# panel-mount-orafice-mk-1.net
KiCad netlist of a schematic drawn in EAGLE
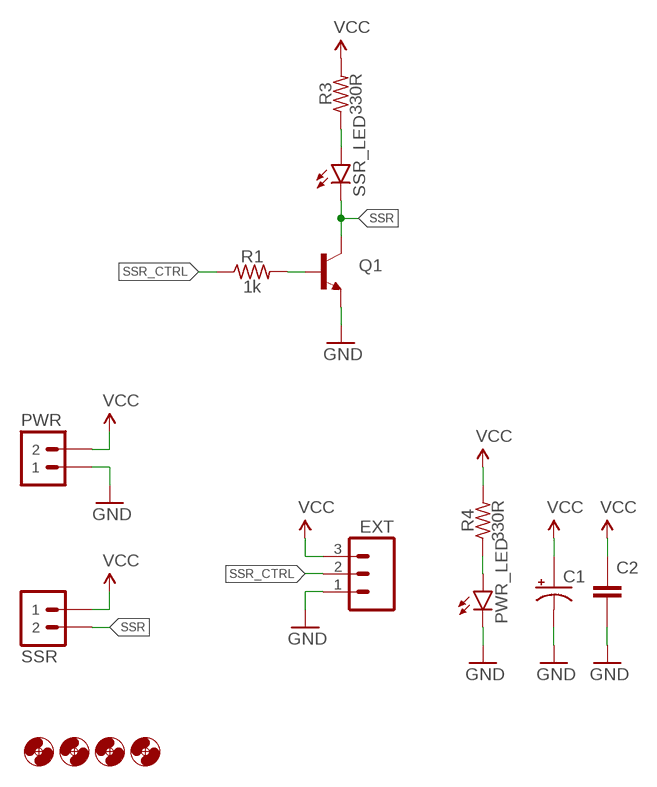
[diagram p0: schematic, sheet 1]

(export (version "E")
  (design (tool "Eeschema 10.0.6"))
  (components
    (comp (ref "C1")
      (value "CAPACITOR-POLARIZEDE3.5-8")
      (footprint "eagle-import:E3,5-8")
      (libsource (lib "eagle-import") (part "CAPACITOR-POLARIZEDE3.5-8"))
    )
    (comp (ref "C2")
      (value "CAPACITOR-CERAMIC025-024X044")
      (footprint "eagle-import:C025-024X044")
      (libsource (lib "eagle-import") (part "CAPACITOR-CERAMIC025-024X044"))
    )
    (comp (ref "EXT")
      (value "M03JST-XH-RA-PTH")
      (footprint "eagle-import:JST-3-XH-RA-PTH")
      (libsource (lib "eagle-import") (part "M03JST-XH-RA-PTH"))
    )
    (comp (ref "H1")
      (value "HOLE#2")
      (footprint "eagle-import:HOLE-#2")
      (libsource (lib "eagle-import") (part "HOLE#2"))
    )
    (comp (ref "H2")
      (value "HOLE#2")
      (footprint "eagle-import:HOLE-#2")
      (libsource (lib "eagle-import") (part "HOLE#2"))
    )
    (comp (ref "H3")
      (value "HOLE#2")
      (footprint "eagle-import:HOLE-#2")
      (libsource (lib "eagle-import") (part "HOLE#2"))
    )
    (comp (ref "H4")
      (value "HOLE#2")
      (footprint "eagle-import:HOLE-#2")
      (libsource (lib "eagle-import") (part "HOLE#2"))
    )
    (comp (ref "PWR")
      (value "M02JST-PTH-VERT")
      (footprint "eagle-import:JST-2-PH-VERT-PTH")
      (libsource (lib "eagle-import") (part "M02JST-PTH-VERT"))
    )
    (comp (ref "PWR_LED")
      (value "LED3MM")
      (footprint "eagle-import:LED3MM")
      (libsource (lib "eagle-import") (part "LED3MM"))
    )
    (comp (ref "Q1")
      (value "TRANSISTOR_NPNTO-92-AMMO-EBC")
      (footprint "eagle-import:TO-92-AMMO")
      (libsource (lib "eagle-import") (part "TRANSISTOR_NPNTO-92-AMMO-EBC"))
    )
    (comp (ref "R1")
      (value "1k")
      (footprint "eagle-import:RESISTOR-AXIAL-PTH-6.35MM")
      (libsource (lib "eagle-import") (part "RESISTORPTH-AXIAL-6.35MM"))
    )
    (comp (ref "R3")
      (value "330R")
      (footprint "eagle-import:RESISTOR-AXIAL-PTH-6.35MM")
      (libsource (lib "eagle-import") (part "RESISTORPTH-AXIAL-6.35MM"))
    )
    (comp (ref "R4")
      (value "330R")
      (footprint "eagle-import:RESISTOR-AXIAL-PTH-6.35MM")
      (libsource (lib "eagle-import") (part "RESISTORPTH-AXIAL-6.35MM"))
    )
    (comp (ref "SSR")
      (value "M02JST-PTH-VERT")
      (footprint "eagle-import:JST-2-PH-VERT-PTH")
      (libsource (lib "eagle-import") (part "M02JST-PTH-VERT"))
    )
    (comp (ref "SSR_LED")
      (value "LED3MM")
      (footprint "eagle-import:LED3MM")
      (libsource (lib "eagle-import") (part "LED3MM"))
    )
  )
  (nets
    (net (code "1") (name "GND") (class "Default")
      (node (ref "C1") (pin "-") (pinfunction "-_-") (pintype "passive"))
      (node (ref "C2") (pin "2") (pinfunction "2_2") (pintype "passive"))
      (node (ref "EXT") (pin "1") (pinfunction "1_1") (pintype "passive"))
      (node (ref "PWR") (pin "1") (pinfunction "1_1") (pintype "passive"))
      (node (ref "PWR_LED") (pin "K") (pinfunction "C_K") (pintype "passive"))
      (node (ref "Q1") (pin "1") (pinfunction "E_1") (pintype "passive"))
    )
    (net (code "2") (name "Net-(Q1-B)") (class "Default")
      (node (ref "Q1") (pin "2") (pinfunction "B_2") (pintype "passive"))
      (node (ref "R1") (pin "P$2") (pinfunction "2_P$2") (pintype "passive"))
    )
    (net (code "3") (name "Net-(R3-1)") (class "Default")
      (node (ref "R3") (pin "P$1") (pinfunction "1_P$1") (pintype "passive"))
      (node (ref "SSR_LED") (pin "A") (pinfunction "A_A") (pintype "passive"))
    )
    (net (code "4") (name "Net-(R4-1)") (class "Default")
      (node (ref "PWR_LED") (pin "A") (pinfunction "A_A") (pintype "passive"))
      (node (ref "R4") (pin "P$1") (pinfunction "1_P$1") (pintype "passive"))
    )
    (net (code "5") (name "SSR") (class "Default")
      (node (ref "Q1") (pin "3") (pinfunction "C_3") (pintype "passive"))
      (node (ref "SSR") (pin "2") (pinfunction "2_2") (pintype "passive"))
      (node (ref "SSR_LED") (pin "K") (pinfunction "C_K") (pintype "passive"))
    )
    (net (code "6") (name "SSR_CTRL") (class "Default")
      (node (ref "EXT") (pin "2") (pinfunction "2_2") (pintype "passive"))
      (node (ref "R1") (pin "P$1") (pinfunction "1_P$1") (pintype "passive"))
    )
    (net (code "7") (name "VCC") (class "Default")
      (node (ref "C1") (pin "+") (pinfunction "+_+") (pintype "passive"))
      (node (ref "C2") (pin "1") (pinfunction "1_1") (pintype "passive"))
      (node (ref "EXT") (pin "3") (pinfunction "3_3") (pintype "passive"))
      (node (ref "PWR") (pin "2") (pinfunction "2_2") (pintype "passive"))
      (node (ref "R3") (pin "P$2") (pinfunction "2_P$2") (pintype "passive"))
      (node (ref "R4") (pin "P$2") (pinfunction "2_P$2") (pintype "passive"))
      (node (ref "SSR") (pin "1") (pinfunction "1_1") (pintype "passive"))
    )
  )
)
